# PS_DDR4_SODIMM.net
KiCad netlist of a schematic drawn in Altium Designer
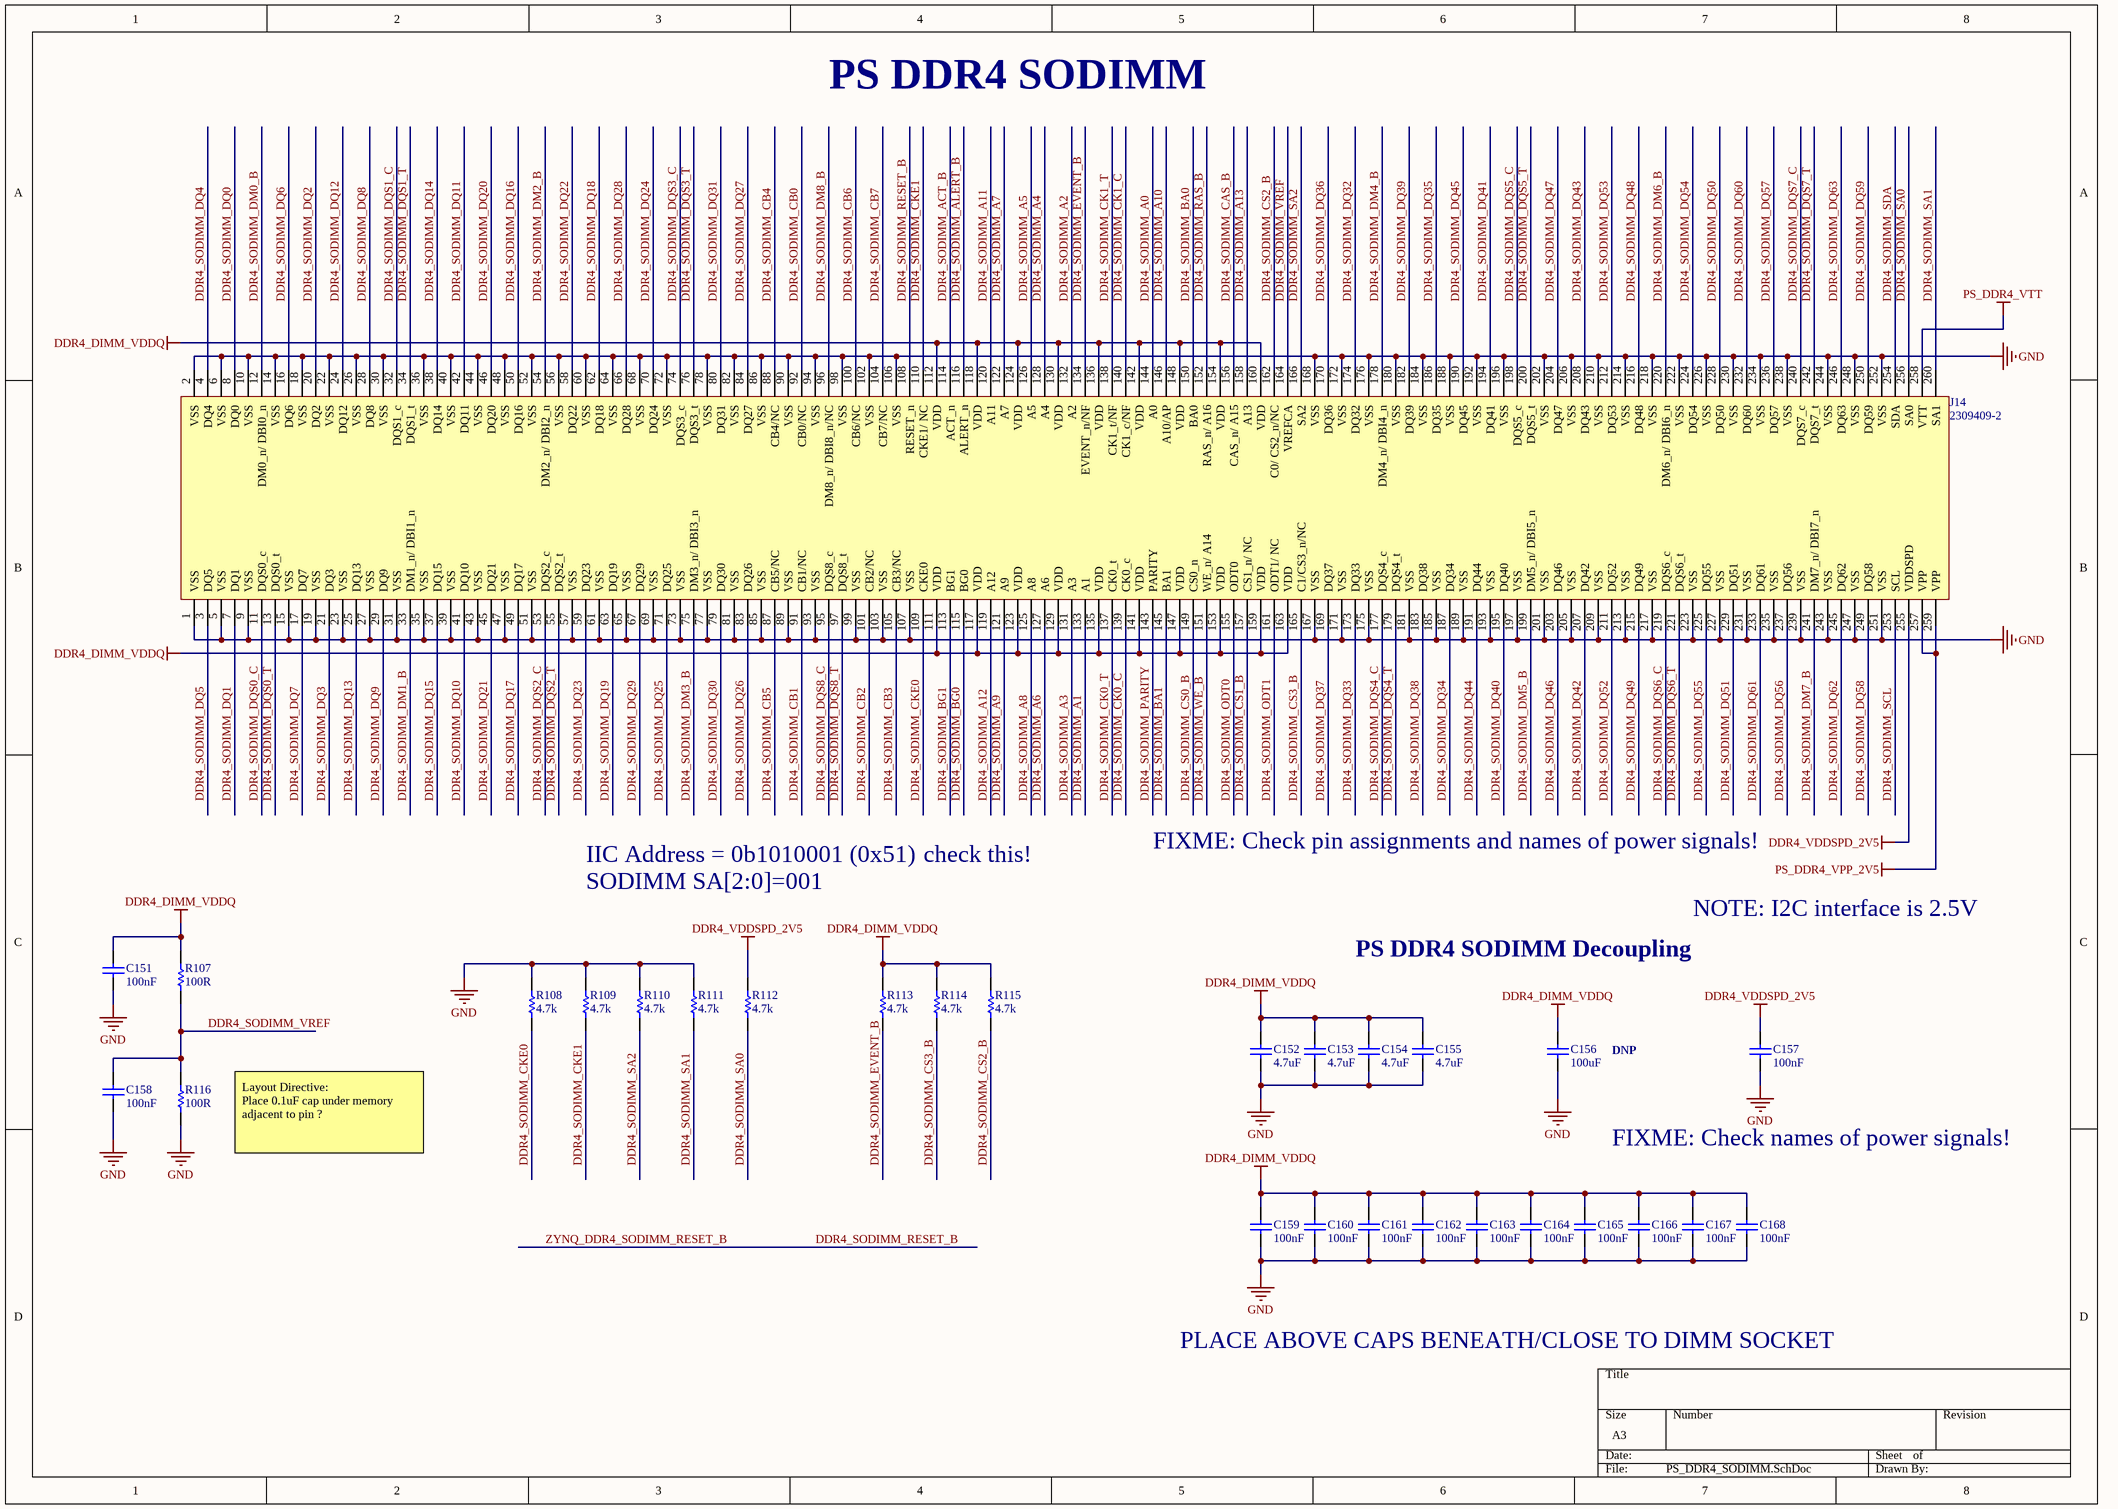
[diagram p0: PS_DDR4_SODIMM.SchDoc]

(export (version "E")
  (design (tool "Eeschema 10.0.6"))
  (components
    (comp (ref "C151")
      (value "100nF")
      (footprint "CAPC1005L_0402")
      (description "CAP CER 0.1UF 25V X7R 0402")
      (fields (field (name "VOLTAGE") "25V") (field (name "TOLERANCE") "10%"))
      (libsource (lib "Ultrascale_SchLib") (part "CAPCER0402X7R100N25V_10T"))
    )
    (comp (ref "C152")
      (value "4.7uF")
      (footprint "CAPC1005L_0402")
      (description "CAP CER 4.7UF 10V X5R 0402")
      (fields (field (name "VOLTAGE") "10V") (field (name "TOLERANCE") "10%"))
      (libsource (lib "Ultrascale_SchLib") (part "CAPCER0402X5R4U710V_10T"))
    )
    (comp (ref "C153")
      (value "4.7uF")
      (footprint "CAPC1005L_0402")
      (description "CAP CER 4.7UF 10V X5R 0402")
      (fields (field (name "VOLTAGE") "10V") (field (name "TOLERANCE") "10%"))
      (libsource (lib "Ultrascale_SchLib") (part "CAPCER0402X5R4U710V_10T"))
    )
    (comp (ref "C154")
      (value "4.7uF")
      (footprint "CAPC1005L_0402")
      (description "CAP CER 4.7UF 10V X5R 0402")
      (fields (field (name "VOLTAGE") "10V") (field (name "TOLERANCE") "10%"))
      (libsource (lib "Ultrascale_SchLib") (part "CAPCER0402X5R4U710V_10T"))
    )
    (comp (ref "C155")
      (value "4.7uF")
      (footprint "CAPC1005L_0402")
      (description "CAP CER 4.7UF 10V X5R 0402")
      (fields (field (name "VOLTAGE") "10V") (field (name "TOLERANCE") "10%"))
      (libsource (lib "Ultrascale_SchLib") (part "CAPCER0402X5R4U710V_10T"))
    )
    (comp (ref "C156")
      (value "100uF")
      (footprint "CAPC3225N_1210")
      (description "CAP CER 100UF 16V X5R 1210")
      (fields (field (name "VOLTAGE") "16V") (field (name "TOLERANCE") "20%"))
      (libsource (lib "Ultrascale_SchLib") (part "CAPCER1210X5R100U16V_20T"))
    )
    (comp (ref "C157")
      (value "100nF")
      (footprint "CAPC1005L_0402")
      (description "CAP CER 0.1UF 25V X7R 0402")
      (fields (field (name "VOLTAGE") "25V") (field (name "TOLERANCE") "10%"))
      (libsource (lib "Ultrascale_SchLib") (part "CAPCER0402X7R100N25V_10T"))
    )
    (comp (ref "C158")
      (value "100nF")
      (footprint "CAPC1005L_0402")
      (description "CAP CER 0.1UF 25V X7R 0402")
      (fields (field (name "VOLTAGE") "25V") (field (name "TOLERANCE") "10%"))
      (libsource (lib "Ultrascale_SchLib") (part "CAPCER0402X7R100N25V_10T"))
    )
    (comp (ref "C159")
      (value "100nF")
      (footprint "CAPC1005L_0402")
      (description "CAP CER 0.1UF 25V X7R 0402")
      (fields (field (name "VOLTAGE") "25V") (field (name "TOLERANCE") "10%"))
      (libsource (lib "Ultrascale_SchLib") (part "CAPCER0402X7R100N25V_10T"))
    )
    (comp (ref "C160")
      (value "100nF")
      (footprint "CAPC1005L_0402")
      (description "CAP CER 0.1UF 25V X7R 0402")
      (fields (field (name "VOLTAGE") "25V") (field (name "TOLERANCE") "10%"))
      (libsource (lib "Ultrascale_SchLib") (part "CAPCER0402X7R100N25V_10T"))
    )
    (comp (ref "C161")
      (value "100nF")
      (footprint "CAPC1005L_0402")
      (description "CAP CER 0.1UF 25V X7R 0402")
      (fields (field (name "VOLTAGE") "25V") (field (name "TOLERANCE") "10%"))
      (libsource (lib "Ultrascale_SchLib") (part "CAPCER0402X7R100N25V_10T"))
    )
    (comp (ref "C162")
      (value "100nF")
      (footprint "CAPC1005L_0402")
      (description "CAP CER 0.1UF 25V X7R 0402")
      (fields (field (name "VOLTAGE") "25V") (field (name "TOLERANCE") "10%"))
      (libsource (lib "Ultrascale_SchLib") (part "CAPCER0402X7R100N25V_10T"))
    )
    (comp (ref "C163")
      (value "100nF")
      (footprint "CAPC1005L_0402")
      (description "CAP CER 0.1UF 25V X7R 0402")
      (fields (field (name "VOLTAGE") "25V") (field (name "TOLERANCE") "10%"))
      (libsource (lib "Ultrascale_SchLib") (part "CAPCER0402X7R100N25V_10T"))
    )
    (comp (ref "C164")
      (value "100nF")
      (footprint "CAPC1005L_0402")
      (description "CAP CER 0.1UF 25V X7R 0402")
      (fields (field (name "VOLTAGE") "25V") (field (name "TOLERANCE") "10%"))
      (libsource (lib "Ultrascale_SchLib") (part "CAPCER0402X7R100N25V_10T"))
    )
    (comp (ref "C165")
      (value "100nF")
      (footprint "CAPC1005L_0402")
      (description "CAP CER 0.1UF 25V X7R 0402")
      (fields (field (name "VOLTAGE") "25V") (field (name "TOLERANCE") "10%"))
      (libsource (lib "Ultrascale_SchLib") (part "CAPCER0402X7R100N25V_10T"))
    )
    (comp (ref "C166")
      (value "100nF")
      (footprint "CAPC1005L_0402")
      (description "CAP CER 0.1UF 25V X7R 0402")
      (fields (field (name "VOLTAGE") "25V") (field (name "TOLERANCE") "10%"))
      (libsource (lib "Ultrascale_SchLib") (part "CAPCER0402X7R100N25V_10T"))
    )
    (comp (ref "C167")
      (value "100nF")
      (footprint "CAPC1005L_0402")
      (description "CAP CER 0.1UF 25V X7R 0402")
      (fields (field (name "VOLTAGE") "25V") (field (name "TOLERANCE") "10%"))
      (libsource (lib "Ultrascale_SchLib") (part "CAPCER0402X7R100N25V_10T"))
    )
    (comp (ref "C168")
      (value "100nF")
      (footprint "CAPC1005L_0402")
      (description "CAP CER 0.1UF 25V X7R 0402")
      (fields (field (name "VOLTAGE") "25V") (field (name "TOLERANCE") "10%"))
      (libsource (lib "Ultrascale_SchLib") (part "CAPCER0402X7R100N25V_10T"))
    )
    (comp (ref "J14")
      (value "2309409-2")
      (footprint "DDR4_SODIMM_MATING")
      (description "DDR4 SODIMM 260P 5.2H STD")
      (libsource (lib "Ultrascale_SchLib") (part "2309409-2"))
    )
    (comp (ref "R107")
      (value "100R")
      (footprint "RESC1005L_0402")
      (description "RES SMD 100 OHM 1% 1/10W 0402")
      (fields (field (name "POWER") "1/10W") (field (name "TOLERANCE") "1%"))
      (libsource (lib "Ultrascale_SchLib") (part "RES0402_100R_0W1_1T"))
    )
    (comp (ref "R108")
      (value "4.7k")
      (footprint "RESC1005L_0402")
      (description "RES SMD 4.7K OHM 1% 1/10W 0402")
      (fields (field (name "POWER") "1/10W") (field (name "TOLERANCE") "1%"))
      (libsource (lib "Ultrascale_SchLib") (part "RES0402_4K7_0W1_1T"))
    )
    (comp (ref "R109")
      (value "4.7k")
      (footprint "RESC1005L_0402")
      (description "RES SMD 4.7K OHM 1% 1/10W 0402")
      (fields (field (name "POWER") "1/10W") (field (name "TOLERANCE") "1%"))
      (libsource (lib "Ultrascale_SchLib") (part "RES0402_4K7_0W1_1T"))
    )
    (comp (ref "R110")
      (value "4.7k")
      (footprint "RESC1005L_0402")
      (description "RES SMD 4.7K OHM 1% 1/10W 0402")
      (fields (field (name "POWER") "1/10W") (field (name "TOLERANCE") "1%"))
      (libsource (lib "Ultrascale_SchLib") (part "RES0402_4K7_0W1_1T"))
    )
    (comp (ref "R111")
      (value "4.7k")
      (footprint "RESC1005L_0402")
      (description "RES SMD 4.7K OHM 1% 1/10W 0402")
      (fields (field (name "POWER") "1/10W") (field (name "TOLERANCE") "1%"))
      (libsource (lib "Ultrascale_SchLib") (part "RES0402_4K7_0W1_1T"))
    )
    (comp (ref "R112")
      (value "4.7k")
      (footprint "RESC1005L_0402")
      (description "RES SMD 4.7K OHM 1% 1/10W 0402")
      (fields (field (name "POWER") "1/10W") (field (name "TOLERANCE") "1%"))
      (libsource (lib "Ultrascale_SchLib") (part "RES0402_4K7_0W1_1T"))
    )
    (comp (ref "R113")
      (value "4.7k")
      (footprint "RESC1005L_0402")
      (description "RES SMD 4.7K OHM 1% 1/10W 0402")
      (fields (field (name "POWER") "1/10W") (field (name "TOLERANCE") "1%"))
      (libsource (lib "Ultrascale_SchLib") (part "RES0402_4K7_0W1_1T"))
    )
    (comp (ref "R114")
      (value "4.7k")
      (footprint "RESC1005L_0402")
      (description "RES SMD 4.7K OHM 1% 1/10W 0402")
      (fields (field (name "POWER") "1/10W") (field (name "TOLERANCE") "1%"))
      (libsource (lib "Ultrascale_SchLib") (part "RES0402_4K7_0W1_1T"))
    )
    (comp (ref "R115")
      (value "4.7k")
      (footprint "RESC1005L_0402")
      (description "RES SMD 4.7K OHM 1% 1/10W 0402")
      (fields (field (name "POWER") "1/10W") (field (name "TOLERANCE") "1%"))
      (libsource (lib "Ultrascale_SchLib") (part "RES0402_4K7_0W1_1T"))
    )
    (comp (ref "R116")
      (value "100R")
      (footprint "RESC1005L_0402")
      (description "RES SMD 100 OHM 1% 1/10W 0402")
      (fields (field (name "POWER") "1/10W") (field (name "TOLERANCE") "1%"))
      (libsource (lib "Ultrascale_SchLib") (part "RES0402_100R_0W1_1T"))
    )
  )
  (nets
    (net (code "1") (name "/DDR4_SODIMM_A0") (class "Default")
      (node (ref "J14") (pin "144") (pinfunction "A0_144") (pintype "power_in"))
    )
    (net (code "2") (name "/DDR4_SODIMM_A1") (class "Default")
      (node (ref "J14") (pin "133") (pinfunction "A1_133") (pintype "power_in"))
    )
    (net (code "3") (name "/DDR4_SODIMM_A2") (class "Default")
      (node (ref "J14") (pin "132") (pinfunction "A2_132") (pintype "power_in"))
    )
    (net (code "4") (name "/DDR4_SODIMM_A3") (class "Default")
      (node (ref "J14") (pin "131") (pinfunction "A3_131") (pintype "power_in"))
    )
    (net (code "5") (name "/DDR4_SODIMM_A4") (class "Default")
      (node (ref "J14") (pin "128") (pinfunction "A4_128") (pintype "power_in"))
    )
    (net (code "6") (name "/DDR4_SODIMM_A5") (class "Default")
      (node (ref "J14") (pin "126") (pinfunction "A5_126") (pintype "power_in"))
    )
    (net (code "7") (name "/DDR4_SODIMM_A6") (class "Default")
      (node (ref "J14") (pin "127") (pinfunction "A6_127") (pintype "power_in"))
    )
    (net (code "8") (name "/DDR4_SODIMM_A7") (class "Default")
      (node (ref "J14") (pin "122") (pinfunction "A7_122") (pintype "power_in"))
    )
    (net (code "9") (name "/DDR4_SODIMM_A8") (class "Default")
      (node (ref "J14") (pin "125") (pinfunction "A8_125") (pintype "power_in"))
    )
    (net (code "10") (name "/DDR4_SODIMM_A9") (class "Default")
      (node (ref "J14") (pin "121") (pinfunction "A9_121") (pintype "power_in"))
    )
    (net (code "11") (name "/DDR4_SODIMM_A10") (class "Default")
      (node (ref "J14") (pin "146") (pinfunction "A10/AP_146") (pintype "power_in"))
    )
    (net (code "12") (name "/DDR4_SODIMM_A11") (class "Default")
      (node (ref "J14") (pin "120") (pinfunction "A11_120") (pintype "power_in"))
    )
    (net (code "13") (name "/DDR4_SODIMM_A12") (class "Default")
      (node (ref "J14") (pin "119") (pinfunction "A12_119") (pintype "power_in"))
    )
    (net (code "14") (name "/DDR4_SODIMM_A13") (class "Default")
      (node (ref "J14") (pin "158") (pinfunction "A13_158") (pintype "power_in"))
    )
    (net (code "15") (name "/DDR4_SODIMM_ACT_B") (class "Default")
      (node (ref "J14") (pin "114") (pinfunction "ACT_n_114") (pintype "power_in"))
    )
    (net (code "16") (name "/DDR4_SODIMM_ALERT_B") (class "Default")
      (node (ref "J14") (pin "116") (pinfunction "ALERT_n_116") (pintype "power_in"))
    )
    (net (code "17") (name "/DDR4_SODIMM_BA0") (class "Default")
      (node (ref "J14") (pin "150") (pinfunction "BA0_150") (pintype "power_in"))
    )
    (net (code "18") (name "/DDR4_SODIMM_BA1") (class "Default")
      (node (ref "J14") (pin "145") (pinfunction "BA1_145") (pintype "power_in"))
    )
    (net (code "19") (name "/DDR4_SODIMM_BG0") (class "Default")
      (node (ref "J14") (pin "115") (pinfunction "BG0_115") (pintype "power_in"))
    )
    (net (code "20") (name "/DDR4_SODIMM_BG1") (class "Default")
      (node (ref "J14") (pin "113") (pinfunction "BG1_113") (pintype "power_in"))
    )
    (net (code "21") (name "/DDR4_SODIMM_CAS_B") (class "Default")
      (node (ref "J14") (pin "156") (pinfunction "CAS_n/_A15_156") (pintype "power_in"))
    )
    (net (code "22") (name "/DDR4_SODIMM_CB0") (class "Default")
      (node (ref "J14") (pin "92") (pinfunction "CB0/NC_92") (pintype "power_in"))
    )
    (net (code "23") (name "/DDR4_SODIMM_CB1") (class "Default")
      (node (ref "J14") (pin "91") (pinfunction "CB1/NC_91") (pintype "power_in"))
    )
    (net (code "24") (name "/DDR4_SODIMM_CB2") (class "Default")
      (node (ref "J14") (pin "101") (pinfunction "CB2/NC_101") (pintype "power_in"))
    )
    (net (code "25") (name "/DDR4_SODIMM_CB3") (class "Default")
      (node (ref "J14") (pin "105") (pinfunction "CB3/NC_105") (pintype "power_in"))
    )
    (net (code "26") (name "/DDR4_SODIMM_CB4") (class "Default")
      (node (ref "J14") (pin "88") (pinfunction "CB4/NC_88") (pintype "power_in"))
    )
    (net (code "27") (name "/DDR4_SODIMM_CB5") (class "Default")
      (node (ref "J14") (pin "87") (pinfunction "CB5/NC_87") (pintype "power_in"))
    )
    (net (code "28") (name "/DDR4_SODIMM_CB6") (class "Default")
      (node (ref "J14") (pin "100") (pinfunction "CB6/NC_100") (pintype "power_in"))
    )
    (net (code "29") (name "/DDR4_SODIMM_CB7") (class "Default")
      (node (ref "J14") (pin "104") (pinfunction "CB7/NC_104") (pintype "power_in"))
    )
    (net (code "30") (name "/DDR4_SODIMM_CK0_C") (class "Default")
      (node (ref "J14") (pin "139") (pinfunction "CK0_c_139") (pintype "power_in"))
    )
    (net (code "31") (name "/DDR4_SODIMM_CK0_T") (class "Default")
      (node (ref "J14") (pin "137") (pinfunction "CK0_t_137") (pintype "power_in"))
    )
    (net (code "32") (name "/DDR4_SODIMM_CK1_C") (class "Default")
      (node (ref "J14") (pin "140") (pinfunction "CK1_c/NF_140") (pintype "power_in"))
    )
    (net (code "33") (name "/DDR4_SODIMM_CK1_T") (class "Default")
      (node (ref "J14") (pin "138") (pinfunction "CK1_t/NF_138") (pintype "power_in"))
    )
    (net (code "34") (name "/DDR4_SODIMM_CKE0") (class "Default")
      (node (ref "J14") (pin "109") (pinfunction "CKE0_109") (pintype "power_in"))
      (node (ref "R108") (pin "1") (pinfunction "1_1") (pintype "passive"))
    )
    (net (code "35") (name "/DDR4_SODIMM_CKE1") (class "Default")
      (node (ref "J14") (pin "110") (pinfunction "CKE1/_NC_110") (pintype "power_in"))
      (node (ref "R109") (pin "1") (pinfunction "1_1") (pintype "passive"))
    )
    (net (code "36") (name "/DDR4_SODIMM_CS0_B") (class "Default")
      (node (ref "J14") (pin "149") (pinfunction "CS0_n_149") (pintype "power_in"))
    )
    (net (code "37") (name "/DDR4_SODIMM_CS1_B") (class "Default")
      (node (ref "J14") (pin "157") (pinfunction "CS1_n/_NC_157") (pintype "power_in"))
    )
    (net (code "38") (name "/DDR4_SODIMM_CS2_B") (class "Default")
      (node (ref "J14") (pin "162") (pinfunction "C0/_CS2_n/NC_162") (pintype "power_in"))
      (node (ref "R115") (pin "1") (pinfunction "1_1") (pintype "passive"))
    )
    (net (code "39") (name "/DDR4_SODIMM_CS3_B") (class "Default")
      (node (ref "J14") (pin "165") (pinfunction "C1/CS3_n/NC_165") (pintype "power_in"))
      (node (ref "R114") (pin "1") (pinfunction "1_1") (pintype "passive"))
    )
    (net (code "40") (name "/DDR4_SODIMM_DM0_B") (class "Default")
      (node (ref "J14") (pin "12") (pinfunction "DM0_n/_DBI0_n_12") (pintype "power_in"))
    )
    (net (code "41") (name "/DDR4_SODIMM_DM1_B") (class "Default")
      (node (ref "J14") (pin "33") (pinfunction "DM1_n/_DBI1_n_33") (pintype "power_in"))
    )
    (net (code "42") (name "/DDR4_SODIMM_DM2_B") (class "Default")
      (node (ref "J14") (pin "54") (pinfunction "DM2_n/_DBI2_n_54") (pintype "power_in"))
    )
    (net (code "43") (name "/DDR4_SODIMM_DM3_B") (class "Default")
      (node (ref "J14") (pin "75") (pinfunction "DM3_n/_DBI3_n_75") (pintype "power_in"))
    )
    (net (code "44") (name "/DDR4_SODIMM_DM4_B") (class "Default")
      (node (ref "J14") (pin "178") (pinfunction "DM4_n/_DBI4_n_178") (pintype "power_in"))
    )
    (net (code "45") (name "/DDR4_SODIMM_DM5_B") (class "Default")
      (node (ref "J14") (pin "199") (pinfunction "DM5_n/_DBI5_n_199") (pintype "power_in"))
    )
    (net (code "46") (name "/DDR4_SODIMM_DM6_B") (class "Default")
      (node (ref "J14") (pin "220") (pinfunction "DM6_n/_DBI6_n_220") (pintype "power_in"))
    )
    (net (code "47") (name "/DDR4_SODIMM_DM7_B") (class "Default")
      (node (ref "J14") (pin "241") (pinfunction "DM7_n/_DBI7_n_241") (pintype "power_in"))
    )
    (net (code "48") (name "/DDR4_SODIMM_DM8_B") (class "Default")
      (node (ref "J14") (pin "96") (pinfunction "DM8_n/_DBI8_n/NC_96") (pintype "power_in"))
    )
    (net (code "49") (name "/DDR4_SODIMM_DQ0") (class "Default")
      (node (ref "J14") (pin "8") (pinfunction "DQ0_8") (pintype "power_in"))
    )
    (net (code "50") (name "/DDR4_SODIMM_DQ1") (class "Default")
      (node (ref "J14") (pin "7") (pinfunction "DQ1_7") (pintype "power_in"))
    )
    (net (code "51") (name "/DDR4_SODIMM_DQ2") (class "Default")
      (node (ref "J14") (pin "20") (pinfunction "DQ2_20") (pintype "power_in"))
    )
    (net (code "52") (name "/DDR4_SODIMM_DQ3") (class "Default")
      (node (ref "J14") (pin "21") (pinfunction "DQ3_21") (pintype "power_in"))
    )
    (net (code "53") (name "/DDR4_SODIMM_DQ4") (class "Default")
      (node (ref "J14") (pin "4") (pinfunction "DQ4_4") (pintype "power_in"))
    )
    (net (code "54") (name "/DDR4_SODIMM_DQ5") (class "Default")
      (node (ref "J14") (pin "3") (pinfunction "DQ5_3") (pintype "power_in"))
    )
    (net (code "55") (name "/DDR4_SODIMM_DQ6") (class "Default")
      (node (ref "J14") (pin "16") (pinfunction "DQ6_16") (pintype "power_in"))
    )
    (net (code "56") (name "/DDR4_SODIMM_DQ7") (class "Default")
      (node (ref "J14") (pin "17") (pinfunction "DQ7_17") (pintype "power_in"))
    )
    (net (code "57") (name "/DDR4_SODIMM_DQ8") (class "Default")
      (node (ref "J14") (pin "28") (pinfunction "DQ8_28") (pintype "power_in"))
    )
    (net (code "58") (name "/DDR4_SODIMM_DQ9") (class "Default")
      (node (ref "J14") (pin "29") (pinfunction "DQ9_29") (pintype "power_in"))
    )
    (net (code "59") (name "/DDR4_SODIMM_DQ10") (class "Default")
      (node (ref "J14") (pin "41") (pinfunction "DQ10_41") (pintype "power_in"))
    )
    (net (code "60") (name "/DDR4_SODIMM_DQ11") (class "Default")
      (node (ref "J14") (pin "42") (pinfunction "DQ11_42") (pintype "power_in"))
    )
    (net (code "61") (name "/DDR4_SODIMM_DQ12") (class "Default")
      (node (ref "J14") (pin "24") (pinfunction "DQ12_24") (pintype "power_in"))
    )
    (net (code "62") (name "/DDR4_SODIMM_DQ13") (class "Default")
      (node (ref "J14") (pin "25") (pinfunction "DQ13_25") (pintype "power_in"))
    )
    (net (code "63") (name "/DDR4_SODIMM_DQ14") (class "Default")
      (node (ref "J14") (pin "38") (pinfunction "DQ14_38") (pintype "power_in"))
    )
    (net (code "64") (name "/DDR4_SODIMM_DQ15") (class "Default")
      (node (ref "J14") (pin "37") (pinfunction "DQ15_37") (pintype "power_in"))
    )
    (net (code "65") (name "/DDR4_SODIMM_DQ16") (class "Default")
      (node (ref "J14") (pin "50") (pinfunction "DQ16_50") (pintype "power_in"))
    )
    (net (code "66") (name "/DDR4_SODIMM_DQ17") (class "Default")
      (node (ref "J14") (pin "49") (pinfunction "DQ17_49") (pintype "power_in"))
    )
    (net (code "67") (name "/DDR4_SODIMM_DQ18") (class "Default")
      (node (ref "J14") (pin "62") (pinfunction "DQ18_62") (pintype "power_in"))
    )
    (net (code "68") (name "/DDR4_SODIMM_DQ19") (class "Default")
      (node (ref "J14") (pin "63") (pinfunction "DQ19_63") (pintype "power_in"))
    )
    (net (code "69") (name "/DDR4_SODIMM_DQ20") (class "Default")
      (node (ref "J14") (pin "46") (pinfunction "DQ20_46") (pintype "power_in"))
    )
    (net (code "70") (name "/DDR4_SODIMM_DQ21") (class "Default")
      (node (ref "J14") (pin "45") (pinfunction "DQ21_45") (pintype "power_in"))
    )
    (net (code "71") (name "/DDR4_SODIMM_DQ22") (class "Default")
      (node (ref "J14") (pin "58") (pinfunction "DQ22_58") (pintype "power_in"))
    )
    (net (code "72") (name "/DDR4_SODIMM_DQ23") (class "Default")
      (node (ref "J14") (pin "59") (pinfunction "DQ23_59") (pintype "power_in"))
    )
    (net (code "73") (name "/DDR4_SODIMM_DQ24") (class "Default")
      (node (ref "J14") (pin "70") (pinfunction "DQ24_70") (pintype "power_in"))
    )
    (net (code "74") (name "/DDR4_SODIMM_DQ25") (class "Default")
      (node (ref "J14") (pin "71") (pinfunction "DQ25_71") (pintype "power_in"))
    )
    (net (code "75") (name "/DDR4_SODIMM_DQ26") (class "Default")
      (node (ref "J14") (pin "83") (pinfunction "DQ26_83") (pintype "power_in"))
    )
    (net (code "76") (name "/DDR4_SODIMM_DQ27") (class "Default")
      (node (ref "J14") (pin "84") (pinfunction "DQ27_84") (pintype "power_in"))
    )
    (net (code "77") (name "/DDR4_SODIMM_DQ28") (class "Default")
      (node (ref "J14") (pin "66") (pinfunction "DQ28_66") (pintype "power_in"))
    )
    (net (code "78") (name "/DDR4_SODIMM_DQ29") (class "Default")
      (node (ref "J14") (pin "67") (pinfunction "DQ29_67") (pintype "power_in"))
    )
    (net (code "79") (name "/DDR4_SODIMM_DQ30") (class "Default")
      (node (ref "J14") (pin "79") (pinfunction "DQ30_79") (pintype "power_in"))
    )
    (net (code "80") (name "/DDR4_SODIMM_DQ31") (class "Default")
      (node (ref "J14") (pin "80") (pinfunction "DQ31_80") (pintype "power_in"))
    )
    (net (code "81") (name "/DDR4_SODIMM_DQ32") (class "Default")
      (node (ref "J14") (pin "174") (pinfunction "DQ32_174") (pintype "power_in"))
    )
    (net (code "82") (name "/DDR4_SODIMM_DQ33") (class "Default")
      (node (ref "J14") (pin "173") (pinfunction "DQ33_173") (pintype "power_in"))
    )
    (net (code "83") (name "/DDR4_SODIMM_DQ34") (class "Default")
      (node (ref "J14") (pin "187") (pinfunction "DQ34_187") (pintype "power_in"))
    )
    (net (code "84") (name "/DDR4_SODIMM_DQ35") (class "Default")
      (node (ref "J14") (pin "186") (pinfunction "DQ35_186") (pintype "power_in"))
    )
    (net (code "85") (name "/DDR4_SODIMM_DQ36") (class "Default")
      (node (ref "J14") (pin "170") (pinfunction "DQ36_170") (pintype "power_in"))
    )
    (net (code "86") (name "/DDR4_SODIMM_DQ37") (class "Default")
      (node (ref "J14") (pin "169") (pinfunction "DQ37_169") (pintype "power_in"))
    )
    (net (code "87") (name "/DDR4_SODIMM_DQ38") (class "Default")
      (node (ref "J14") (pin "183") (pinfunction "DQ38_183") (pintype "power_in"))
    )
    (net (code "88") (name "/DDR4_SODIMM_DQ39") (class "Default")
      (node (ref "J14") (pin "182") (pinfunction "DQ39_182") (pintype "power_in"))
    )
    (net (code "89") (name "/DDR4_SODIMM_DQ40") (class "Default")
      (node (ref "J14") (pin "195") (pinfunction "DQ40_195") (pintype "power_in"))
    )
    (net (code "90") (name "/DDR4_SODIMM_DQ41") (class "Default")
      (node (ref "J14") (pin "194") (pinfunction "DQ41_194") (pintype "power_in"))
    )
    (net (code "91") (name "/DDR4_SODIMM_DQ42") (class "Default")
      (node (ref "J14") (pin "207") (pinfunction "DQ42_207") (pintype "power_in"))
    )
    (net (code "92") (name "/DDR4_SODIMM_DQ43") (class "Default")
      (node (ref "J14") (pin "208") (pinfunction "DQ43_208") (pintype "power_in"))
    )
    (net (code "93") (name "/DDR4_SODIMM_DQ44") (class "Default")
      (node (ref "J14") (pin "191") (pinfunction "DQ44_191") (pintype "power_in"))
    )
    (net (code "94") (name "/DDR4_SODIMM_DQ45") (class "Default")
      (node (ref "J14") (pin "190") (pinfunction "DQ45_190") (pintype "power_in"))
    )
    (net (code "95") (name "/DDR4_SODIMM_DQ46") (class "Default")
      (node (ref "J14") (pin "203") (pinfunction "DQ46_203") (pintype "power_in"))
    )
    (net (code "96") (name "/DDR4_SODIMM_DQ47") (class "Default")
      (node (ref "J14") (pin "204") (pinfunction "DQ47_204") (pintype "power_in"))
    )
    (net (code "97") (name "/DDR4_SODIMM_DQ48") (class "Default")
      (node (ref "J14") (pin "216") (pinfunction "DQ48_216") (pintype "power_in"))
    )
    (net (code "98") (name "/DDR4_SODIMM_DQ49") (class "Default")
      (node (ref "J14") (pin "215") (pinfunction "DQ49_215") (pintype "power_in"))
    )
    (net (code "99") (name "/DDR4_SODIMM_DQ50") (class "Default")
      (node (ref "J14") (pin "228") (pinfunction "DQ50_228") (pintype "power_in"))
    )
    (net (code "100") (name "/DDR4_SODIMM_DQ51") (class "Default")
      (node (ref "J14") (pin "229") (pinfunction "DQ51_229") (pintype "power_in"))
    )
    (net (code "101") (name "/DDR4_SODIMM_DQ52") (class "Default")
      (node (ref "J14") (pin "211") (pinfunction "DQ52_211") (pintype "power_in"))
    )
    (net (code "102") (name "/DDR4_SODIMM_DQ53") (class "Default")
      (node (ref "J14") (pin "212") (pinfunction "DQ53_212") (pintype "power_in"))
    )
    (net (code "103") (name "/DDR4_SODIMM_DQ54") (class "Default")
      (node (ref "J14") (pin "224") (pinfunction "DQ54_224") (pintype "power_in"))
    )
    (net (code "104") (name "/DDR4_SODIMM_DQ55") (class "Default")
      (node (ref "J14") (pin "225") (pinfunction "DQ55_225") (pintype "power_in"))
    )
    (net (code "105") (name "/DDR4_SODIMM_DQ56") (class "Default")
      (node (ref "J14") (pin "237") (pinfunction "DQ56_237") (pintype "power_in"))
    )
    (net (code "106") (name "/DDR4_SODIMM_DQ57") (class "Default")
      (node (ref "J14") (pin "236") (pinfunction "DQ57_236") (pintype "power_in"))
    )
    (net (code "107") (name "/DDR4_SODIMM_DQ58") (class "Default")
      (node (ref "J14") (pin "249") (pinfunction "DQ58_249") (pintype "power_in"))
    )
    (net (code "108") (name "/DDR4_SODIMM_DQ59") (class "Default")
      (node (ref "J14") (pin "250") (pinfunction "DQ59_250") (pintype "power_in"))
    )
    (net (code "109") (name "/DDR4_SODIMM_DQ60") (class "Default")
      (node (ref "J14") (pin "232") (pinfunction "DQ60_232") (pintype "power_in"))
    )
    (net (code "110") (name "/DDR4_SODIMM_DQ61") (class "Default")
      (node (ref "J14") (pin "233") (pinfunction "DQ61_233") (pintype "power_in"))
    )
    (net (code "111") (name "/DDR4_SODIMM_DQ62") (class "Default")
      (node (ref "J14") (pin "245") (pinfunction "DQ62_245") (pintype "power_in"))
    )
    (net (code "112") (name "/DDR4_SODIMM_DQ63") (class "Default")
      (node (ref "J14") (pin "246") (pinfunction "DQ63_246") (pintype "power_in"))
    )
    (net (code "113") (name "/DDR4_SODIMM_DQS0_C") (class "Default")
      (node (ref "J14") (pin "11") (pinfunction "DQS0_c_11") (pintype "power_in"))
    )
    (net (code "114") (name "/DDR4_SODIMM_DQS0_T") (class "Default")
      (node (ref "J14") (pin "13") (pinfunction "DQS0_t_13") (pintype "power_in"))
    )
    (net (code "115") (name "/DDR4_SODIMM_DQS1_C") (class "Default")
      (node (ref "J14") (pin "32") (pinfunction "DQS1_c_32") (pintype "power_in"))
    )
    (net (code "116") (name "/DDR4_SODIMM_DQS1_T") (class "Default")
      (node (ref "J14") (pin "34") (pinfunction "DQS1_t_34") (pintype "power_in"))
    )
    (net (code "117") (name "/DDR4_SODIMM_DQS2_C") (class "Default")
      (node (ref "J14") (pin "53") (pinfunction "DQS2_c_53") (pintype "power_in"))
    )
    (net (code "118") (name "/DDR4_SODIMM_DQS2_T") (class "Default")
      (node (ref "J14") (pin "55") (pinfunction "DQS2_t_55") (pintype "power_in"))
    )
    (net (code "119") (name "/DDR4_SODIMM_DQS3_C") (class "Default")
      (node (ref "J14") (pin "74") (pinfunction "DQS3_c_74") (pintype "power_in"))
    )
    (net (code "120") (name "/DDR4_SODIMM_DQS3_T") (class "Default")
      (node (ref "J14") (pin "76") (pinfunction "DQS3_t_76") (pintype "power_in"))
    )
    (net (code "121") (name "/DDR4_SODIMM_DQS4_C") (class "Default")
      (node (ref "J14") (pin "177") (pinfunction "DQS4_c_177") (pintype "power_in"))
    )
    (net (code "122") (name "/DDR4_SODIMM_DQS4_T") (class "Default")
      (node (ref "J14") (pin "179") (pinfunction "DQS4_t_179") (pintype "power_in"))
    )
    (net (code "123") (name "/DDR4_SODIMM_DQS5_C") (class "Default")
      (node (ref "J14") (pin "198") (pinfunction "DQS5_c_198") (pintype "power_in"))
    )
    (net (code "124") (name "/DDR4_SODIMM_DQS5_T") (class "Default")
      (node (ref "J14") (pin "200") (pinfunction "DQS5_t_200") (pintype "power_in"))
    )
    (net (code "125") (name "/DDR4_SODIMM_DQS6_C") (class "Default")
      (node (ref "J14") (pin "219") (pinfunction "DQS6_c_219") (pintype "power_in"))
    )
    (net (code "126") (name "/DDR4_SODIMM_DQS6_T") (class "Default")
      (node (ref "J14") (pin "221") (pinfunction "DQS6_t_221") (pintype "power_in"))
    )
    (net (code "127") (name "/DDR4_SODIMM_DQS7_C") (class "Default")
      (node (ref "J14") (pin "240") (pinfunction "DQS7_c_240") (pintype "power_in"))
    )
    (net (code "128") (name "/DDR4_SODIMM_DQS7_T") (class "Default")
      (node (ref "J14") (pin "242") (pinfunction "DQS7_t_242") (pintype "power_in"))
    )
    (net (code "129") (name "/DDR4_SODIMM_DQS8_C") (class "Default")
      (node (ref "J14") (pin "95") (pinfunction "DQS8_c_95") (pintype "power_in"))
    )
    (net (code "130") (name "/DDR4_SODIMM_DQS8_T") (class "Default")
      (node (ref "J14") (pin "97") (pinfunction "DQS8_t_97") (pintype "power_in"))
    )
    (net (code "131") (name "/DDR4_SODIMM_EVENT_B") (class "Default")
      (node (ref "J14") (pin "134") (pinfunction "EVENT_n/NF_134") (pintype "power_in"))
      (node (ref "R113") (pin "1") (pinfunction "1_1") (pintype "passive"))
    )
    (net (code "132") (name "/DDR4_SODIMM_ODT0") (class "Default")
      (node (ref "J14") (pin "155") (pinfunction "ODT0_155") (pintype "power_in"))
    )
    (net (code "133") (name "/DDR4_SODIMM_ODT1") (class "Default")
      (node (ref "J14") (pin "161") (pinfunction "ODT1/_NC_161") (pintype "power_in"))
    )
    (net (code "134") (name "/DDR4_SODIMM_PARITY") (class "Default")
      (node (ref "J14") (pin "143") (pinfunction "PARITY_143") (pintype "power_in"))
    )
    (net (code "135") (name "/DDR4_SODIMM_RAS_B") (class "Default")
      (node (ref "J14") (pin "152") (pinfunction "RAS_n/_A16_152") (pintype "power_in"))
    )
    (net (code "136") (name "/DDR4_SODIMM_RESET_B") (class "Default")
      (node (ref "J14") (pin "108") (pinfunction "RESET_n_108") (pintype "power_in"))
    )
    (net (code "137") (name "/DDR4_SODIMM_SA0") (class "Default")
      (node (ref "J14") (pin "256") (pinfunction "SA0_256") (pintype "power_in"))
      (node (ref "R112") (pin "1") (pinfunction "1_1") (pintype "passive"))
    )
    (net (code "138") (name "/DDR4_SODIMM_SA1") (class "Default")
      (node (ref "J14") (pin "260") (pinfunction "SA1_260") (pintype "power_in"))
      (node (ref "R111") (pin "1") (pinfunction "1_1") (pintype "passive"))
    )
    (net (code "139") (name "/DDR4_SODIMM_SA2") (class "Default")
      (node (ref "J14") (pin "166") (pinfunction "SA2_166") (pintype "power_in"))
      (node (ref "R110") (pin "1") (pinfunction "1_1") (pintype "passive"))
    )
    (net (code "140") (name "/DDR4_SODIMM_SCL") (class "Default")
      (node (ref "J14") (pin "253") (pinfunction "SCL_253") (pintype "power_in"))
    )
    (net (code "141") (name "/DDR4_SODIMM_SDA") (class "Default")
      (node (ref "J14") (pin "254") (pinfunction "SDA_254") (pintype "power_in"))
    )
    (net (code "142") (name "/DDR4_SODIMM_VREF") (class "Default")
      (node (ref "C158") (pin "2") (pinfunction "2_2") (pintype "passive"))
      (node (ref "J14") (pin "164") (pinfunction "VREFCA_164") (pintype "power_in"))
      (node (ref "R107") (pin "1") (pinfunction "1_1") (pintype "passive"))
      (node (ref "R116") (pin "2") (pinfunction "2_2") (pintype "passive"))
    )
    (net (code "143") (name "/DDR4_SODIMM_WE_B") (class "Default")
      (node (ref "J14") (pin "151") (pinfunction "WE_n/_A14_151") (pintype "power_in"))
    )
    (net (code "144") (name "DDR4_DIMM_VDDQ") (class "Default")
      (node (ref "C151") (pin "2") (pinfunction "2_2") (pintype "passive"))
      (node (ref "C152") (pin "2") (pinfunction "2_2") (pintype "passive"))
      (node (ref "C153") (pin "2") (pinfunction "2_2") (pintype "passive"))
      (node (ref "C154") (pin "2") (pinfunction "2_2") (pintype "passive"))
      (node (ref "C155") (pin "2") (pinfunction "2_2") (pintype "passive"))
      (node (ref "C156") (pin "2") (pinfunction "2_2") (pintype "passive"))
      (node (ref "C159") (pin "2") (pinfunction "2_2") (pintype "passive"))
      (node (ref "C160") (pin "2") (pinfunction "2_2") (pintype "passive"))
      (node (ref "C161") (pin "2") (pinfunction "2_2") (pintype "passive"))
      (node (ref "C162") (pin "2") (pinfunction "2_2") (pintype "passive"))
      (node (ref "C163") (pin "2") (pinfunction "2_2") (pintype "passive"))
      (node (ref "C164") (pin "2") (pinfunction "2_2") (pintype "passive"))
      (node (ref "C165") (pin "2") (pinfunction "2_2") (pintype "passive"))
      (node (ref "C166") (pin "2") (pinfunction "2_2") (pintype "passive"))
      (node (ref "C167") (pin "2") (pinfunction "2_2") (pintype "passive"))
      (node (ref "C168") (pin "2") (pinfunction "2_2") (pintype "passive"))
      (node (ref "J14") (pin "111") (pinfunction "VDD_111") (pintype "power_in"))
      (node (ref "J14") (pin "112") (pinfunction "VDD_112") (pintype "power_in"))
      (node (ref "J14") (pin "117") (pinfunction "VDD_117") (pintype "power_in"))
      (node (ref "J14") (pin "118") (pinfunction "VDD_118") (pintype "power_in"))
      (node (ref "J14") (pin "123") (pinfunction "VDD_123") (pintype "power_in"))
      (node (ref "J14") (pin "124") (pinfunction "VDD_124") (pintype "power_in"))
      (node (ref "J14") (pin "129") (pinfunction "VDD_129") (pintype "power_in"))
      (node (ref "J14") (pin "130") (pinfunction "VDD_130") (pintype "power_in"))
      (node (ref "J14") (pin "135") (pinfunction "VDD_135") (pintype "power_in"))
      (node (ref "J14") (pin "136") (pinfunction "VDD_136") (pintype "power_in"))
      (node (ref "J14") (pin "141") (pinfunction "VDD_141") (pintype "power_in"))
      (node (ref "J14") (pin "142") (pinfunction "VDD_142") (pintype "power_in"))
      (node (ref "J14") (pin "147") (pinfunction "VDD_147") (pintype "power_in"))
      (node (ref "J14") (pin "148") (pinfunction "VDD_148") (pintype "power_in"))
      (node (ref "J14") (pin "153") (pinfunction "VDD_153") (pintype "power_in"))
      (node (ref "J14") (pin "154") (pinfunction "VDD_154") (pintype "power_in"))
      (node (ref "J14") (pin "159") (pinfunction "VDD_159") (pintype "power_in"))
      (node (ref "J14") (pin "160") (pinfunction "VDD_160") (pintype "power_in"))
      (node (ref "J14") (pin "163") (pinfunction "VDD_163") (pintype "power_in"))
      (node (ref "R107") (pin "2") (pinfunction "2_2") (pintype "passive"))
      (node (ref "R113") (pin "2") (pinfunction "2_2") (pintype "passive"))
      (node (ref "R114") (pin "2") (pinfunction "2_2") (pintype "passive"))
      (node (ref "R115") (pin "2") (pinfunction "2_2") (pintype "passive"))
    )
    (net (code "145") (name "DDR4_VDDSPD_2V5") (class "Default")
      (node (ref "C157") (pin "2") (pinfunction "2_2") (pintype "passive"))
      (node (ref "J14") (pin "255") (pinfunction "VDDSPD_255") (pintype "power_in"))
      (node (ref "R112") (pin "2") (pinfunction "2_2") (pintype "passive"))
    )
    (net (code "146") (name "GND") (class "Default")
      (node (ref "C151") (pin "1") (pinfunction "1_1") (pintype "passive"))
      (node (ref "C152") (pin "1") (pinfunction "1_1") (pintype "passive"))
      (node (ref "C153") (pin "1") (pinfunction "1_1") (pintype "passive"))
      (node (ref "C154") (pin "1") (pinfunction "1_1") (pintype "passive"))
      (node (ref "C155") (pin "1") (pinfunction "1_1") (pintype "passive"))
      (node (ref "C156") (pin "1") (pinfunction "1_1") (pintype "passive"))
      (node (ref "C157") (pin "1") (pinfunction "1_1") (pintype "passive"))
      (node (ref "C158") (pin "1") (pinfunction "1_1") (pintype "passive"))
      (node (ref "C159") (pin "1") (pinfunction "1_1") (pintype "passive"))
      (node (ref "C160") (pin "1") (pinfunction "1_1") (pintype "passive"))
      (node (ref "C161") (pin "1") (pinfunction "1_1") (pintype "passive"))
      (node (ref "C162") (pin "1") (pinfunction "1_1") (pintype "passive"))
      (node (ref "C163") (pin "1") (pinfunction "1_1") (pintype "passive"))
      (node (ref "C164") (pin "1") (pinfunction "1_1") (pintype "passive"))
      (node (ref "C165") (pin "1") (pinfunction "1_1") (pintype "passive"))
      (node (ref "C166") (pin "1") (pinfunction "1_1") (pintype "passive"))
      (node (ref "C167") (pin "1") (pinfunction "1_1") (pintype "passive"))
      (node (ref "C168") (pin "1") (pinfunction "1_1") (pintype "passive"))
      (node (ref "J14") (pin "1") (pinfunction "VSS_1") (pintype "power_in"))
      (node (ref "J14") (pin "10") (pinfunction "VSS_10") (pintype "power_in"))
      (node (ref "J14") (pin "102") (pinfunction "VSS_102") (pintype "power_in"))
      (node (ref "J14") (pin "103") (pinfunction "VSS_103") (pintype "power_in"))
      (node (ref "J14") (pin "106") (pinfunction "VSS_106") (pintype "power_in"))
      (node (ref "J14") (pin "107") (pinfunction "VSS_107") (pintype "power_in"))
      (node (ref "J14") (pin "14") (pinfunction "VSS_14") (pintype "power_in"))
      (node (ref "J14") (pin "15") (pinfunction "VSS_15") (pintype "power_in"))
      (node (ref "J14") (pin "167") (pinfunction "VSS_167") (pintype "power_in"))
      (node (ref "J14") (pin "168") (pinfunction "VSS_168") (pintype "power_in"))
      (node (ref "J14") (pin "171") (pinfunction "VSS_171") (pintype "power_in"))
      (node (ref "J14") (pin "172") (pinfunction "VSS_172") (pintype "power_in"))
      (node (ref "J14") (pin "175") (pinfunction "VSS_175") (pintype "power_in"))
      (node (ref "J14") (pin "176") (pinfunction "VSS_176") (pintype "power_in"))
      (node (ref "J14") (pin "18") (pinfunction "VSS_18") (pintype "power_in"))
      (node (ref "J14") (pin "180") (pinfunction "VSS_180") (pintype "power_in"))
      (node (ref "J14") (pin "181") (pinfunction "VSS_181") (pintype "power_in"))
      (node (ref "J14") (pin "184") (pinfunction "VSS_184") (pintype "power_in"))
      (node (ref "J14") (pin "185") (pinfunction "VSS_185") (pintype "power_in"))
      (node (ref "J14") (pin "188") (pinfunction "VSS_188") (pintype "power_in"))
      (node (ref "J14") (pin "189") (pinfunction "VSS_189") (pintype "power_in"))
      (node (ref "J14") (pin "19") (pinfunction "VSS_19") (pintype "power_in"))
      (node (ref "J14") (pin "192") (pinfunction "VSS_192") (pintype "power_in"))
      (node (ref "J14") (pin "193") (pinfunction "VSS_193") (pintype "power_in"))
      (node (ref "J14") (pin "196") (pinfunction "VSS_196") (pintype "power_in"))
      (node (ref "J14") (pin "197") (pinfunction "VSS_197") (pintype "power_in"))
      (node (ref "J14") (pin "2") (pinfunction "VSS_2") (pintype "power_in"))
      (node (ref "J14") (pin "201") (pinfunction "VSS_201") (pintype "power_in"))
      (node (ref "J14") (pin "202") (pinfunction "VSS_202") (pintype "power_in"))
      (node (ref "J14") (pin "205") (pinfunction "VSS_205") (pintype "power_in"))
      (node (ref "J14") (pin "206") (pinfunction "VSS_206") (pintype "power_in"))
      (node (ref "J14") (pin "209") (pinfunction "VSS_209") (pintype "power_in"))
      (node (ref "J14") (pin "210") (pinfunction "VSS_210") (pintype "power_in"))
      (node (ref "J14") (pin "213") (pinfunction "VSS_213") (pintype "power_in"))
      (node (ref "J14") (pin "214") (pinfunction "VSS_214") (pintype "power_in"))
      (node (ref "J14") (pin "217") (pinfunction "VSS_217") (pintype "power_in"))
      (node (ref "J14") (pin "218") (pinfunction "VSS_218") (pintype "power_in"))
      (node (ref "J14") (pin "22") (pinfunction "VSS_22") (pintype "power_in"))
      (node (ref "J14") (pin "222") (pinfunction "VSS_222") (pintype "power_in"))
      (node (ref "J14") (pin "223") (pinfunction "VSS_223") (pintype "power_in"))
      (node (ref "J14") (pin "226") (pinfunction "VSS_226") (pintype "power_in"))
      (node (ref "J14") (pin "227") (pinfunction "VSS_227") (pintype "power_in"))
      (node (ref "J14") (pin "23") (pinfunction "VSS_23") (pintype "power_in"))
      (node (ref "J14") (pin "230") (pinfunction "VSS_230") (pintype "power_in"))
      (node (ref "J14") (pin "231") (pinfunction "VSS_231") (pintype "power_in"))
      (node (ref "J14") (pin "234") (pinfunction "VSS_234") (pintype "power_in"))
      (node (ref "J14") (pin "235") (pinfunction "VSS_235") (pintype "power_in"))
      (node (ref "J14") (pin "238") (pinfunction "VSS_238") (pintype "power_in"))
      (node (ref "J14") (pin "239") (pinfunction "VSS_239") (pintype "power_in"))
      (node (ref "J14") (pin "243") (pinfunction "VSS_243") (pintype "power_in"))
      (node (ref "J14") (pin "244") (pinfunction "VSS_244") (pintype "power_in"))
      (node (ref "J14") (pin "247") (pinfunction "VSS_247") (pintype "power_in"))
      (node (ref "J14") (pin "248") (pinfunction "VSS_248") (pintype "power_in"))
      (node (ref "J14") (pin "251") (pinfunction "VSS_251") (pintype "power_in"))
      (node (ref "J14") (pin "252") (pinfunction "VSS_252") (pintype "power_in"))
      (node (ref "J14") (pin "26") (pinfunction "VSS_26") (pintype "power_in"))
      (node (ref "J14") (pin "27") (pinfunction "VSS_27") (pintype "power_in"))
      (node (ref "J14") (pin "30") (pinfunction "VSS_30") (pintype "power_in"))
      (node (ref "J14") (pin "31") (pinfunction "VSS_31") (pintype "power_in"))
      (node (ref "J14") (pin "35") (pinfunction "VSS_35") (pintype "power_in"))
      (node (ref "J14") (pin "36") (pinfunction "VSS_36") (pintype "power_in"))
      (node (ref "J14") (pin "39") (pinfunction "VSS_39") (pintype "power_in"))
      (node (ref "J14") (pin "40") (pinfunction "VSS_40") (pintype "power_in"))
      (node (ref "J14") (pin "43") (pinfunction "VSS_43") (pintype "power_in"))
      (node (ref "J14") (pin "44") (pinfunction "VSS_44") (pintype "power_in"))
      (node (ref "J14") (pin "47") (pinfunction "VSS_47") (pintype "power_in"))
      (node (ref "J14") (pin "48") (pinfunction "VSS_48") (pintype "power_in"))
      (node (ref "J14") (pin "5") (pinfunction "VSS_5") (pintype "power_in"))
      (node (ref "J14") (pin "51") (pinfunction "VSS_51") (pintype "power_in"))
      (node (ref "J14") (pin "52") (pinfunction "VSS_52") (pintype "power_in"))
      (node (ref "J14") (pin "56") (pinfunction "VSS_56") (pintype "power_in"))
      (node (ref "J14") (pin "57") (pinfunction "VSS_57") (pintype "power_in"))
      (node (ref "J14") (pin "6") (pinfunction "VSS_6") (pintype "power_in"))
      (node (ref "J14") (pin "60") (pinfunction "VSS_60") (pintype "power_in"))
      (node (ref "J14") (pin "61") (pinfunction "VSS_61") (pintype "power_in"))
      (node (ref "J14") (pin "64") (pinfunction "VSS_64") (pintype "power_in"))
      (node (ref "J14") (pin "65") (pinfunction "VSS_65") (pintype "power_in"))
      (node (ref "J14") (pin "68") (pinfunction "VSS_68") (pintype "power_in"))
      (node (ref "J14") (pin "69") (pinfunction "VSS_69") (pintype "power_in"))
      (node (ref "J14") (pin "72") (pinfunction "VSS_72") (pintype "power_in"))
      (node (ref "J14") (pin "73") (pinfunction "VSS_73") (pintype "power_in"))
      (node (ref "J14") (pin "77") (pinfunction "VSS_77") (pintype "power_in"))
      (node (ref "J14") (pin "78") (pinfunction "VSS_78") (pintype "power_in"))
      (node (ref "J14") (pin "81") (pinfunction "VSS_81") (pintype "power_in"))
      (node (ref "J14") (pin "82") (pinfunction "VSS_82") (pintype "power_in"))
      (node (ref "J14") (pin "85") (pinfunction "VSS_85") (pintype "power_in"))
      (node (ref "J14") (pin "86") (pinfunction "VSS_86") (pintype "power_in"))
      (node (ref "J14") (pin "89") (pinfunction "VSS_89") (pintype "power_in"))
      (node (ref "J14") (pin "9") (pinfunction "VSS_9") (pintype "power_in"))
      (node (ref "J14") (pin "90") (pinfunction "VSS_90") (pintype "power_in"))
      (node (ref "J14") (pin "93") (pinfunction "VSS_93") (pintype "power_in"))
      (node (ref "J14") (pin "94") (pinfunction "VSS_94") (pintype "power_in"))
      (node (ref "J14") (pin "98") (pinfunction "VSS_98") (pintype "power_in"))
      (node (ref "J14") (pin "99") (pinfunction "VSS_99") (pintype "power_in"))
      (node (ref "R108") (pin "2") (pinfunction "2_2") (pintype "passive"))
      (node (ref "R109") (pin "2") (pinfunction "2_2") (pintype "passive"))
      (node (ref "R110") (pin "2") (pinfunction "2_2") (pintype "passive"))
      (node (ref "R111") (pin "2") (pinfunction "2_2") (pintype "passive"))
      (node (ref "R116") (pin "1") (pinfunction "1_1") (pintype "passive"))
    )
    (net (code "147") (name "PS_DDR4_VPP_2V5") (class "Default")
      (node (ref "J14") (pin "257") (pinfunction "VPP_257") (pintype "power_in"))
      (node (ref "J14") (pin "259") (pinfunction "VPP_259") (pintype "power_in"))
    )
    (net (code "148") (name "PS_DDR4_VTT") (class "Default")
      (node (ref "J14") (pin "258") (pinfunction "VTT_258") (pintype "power_in"))
    )
  )
)
